# motherboard.net
KiCad netlist of a schematic drawn in EAGLE
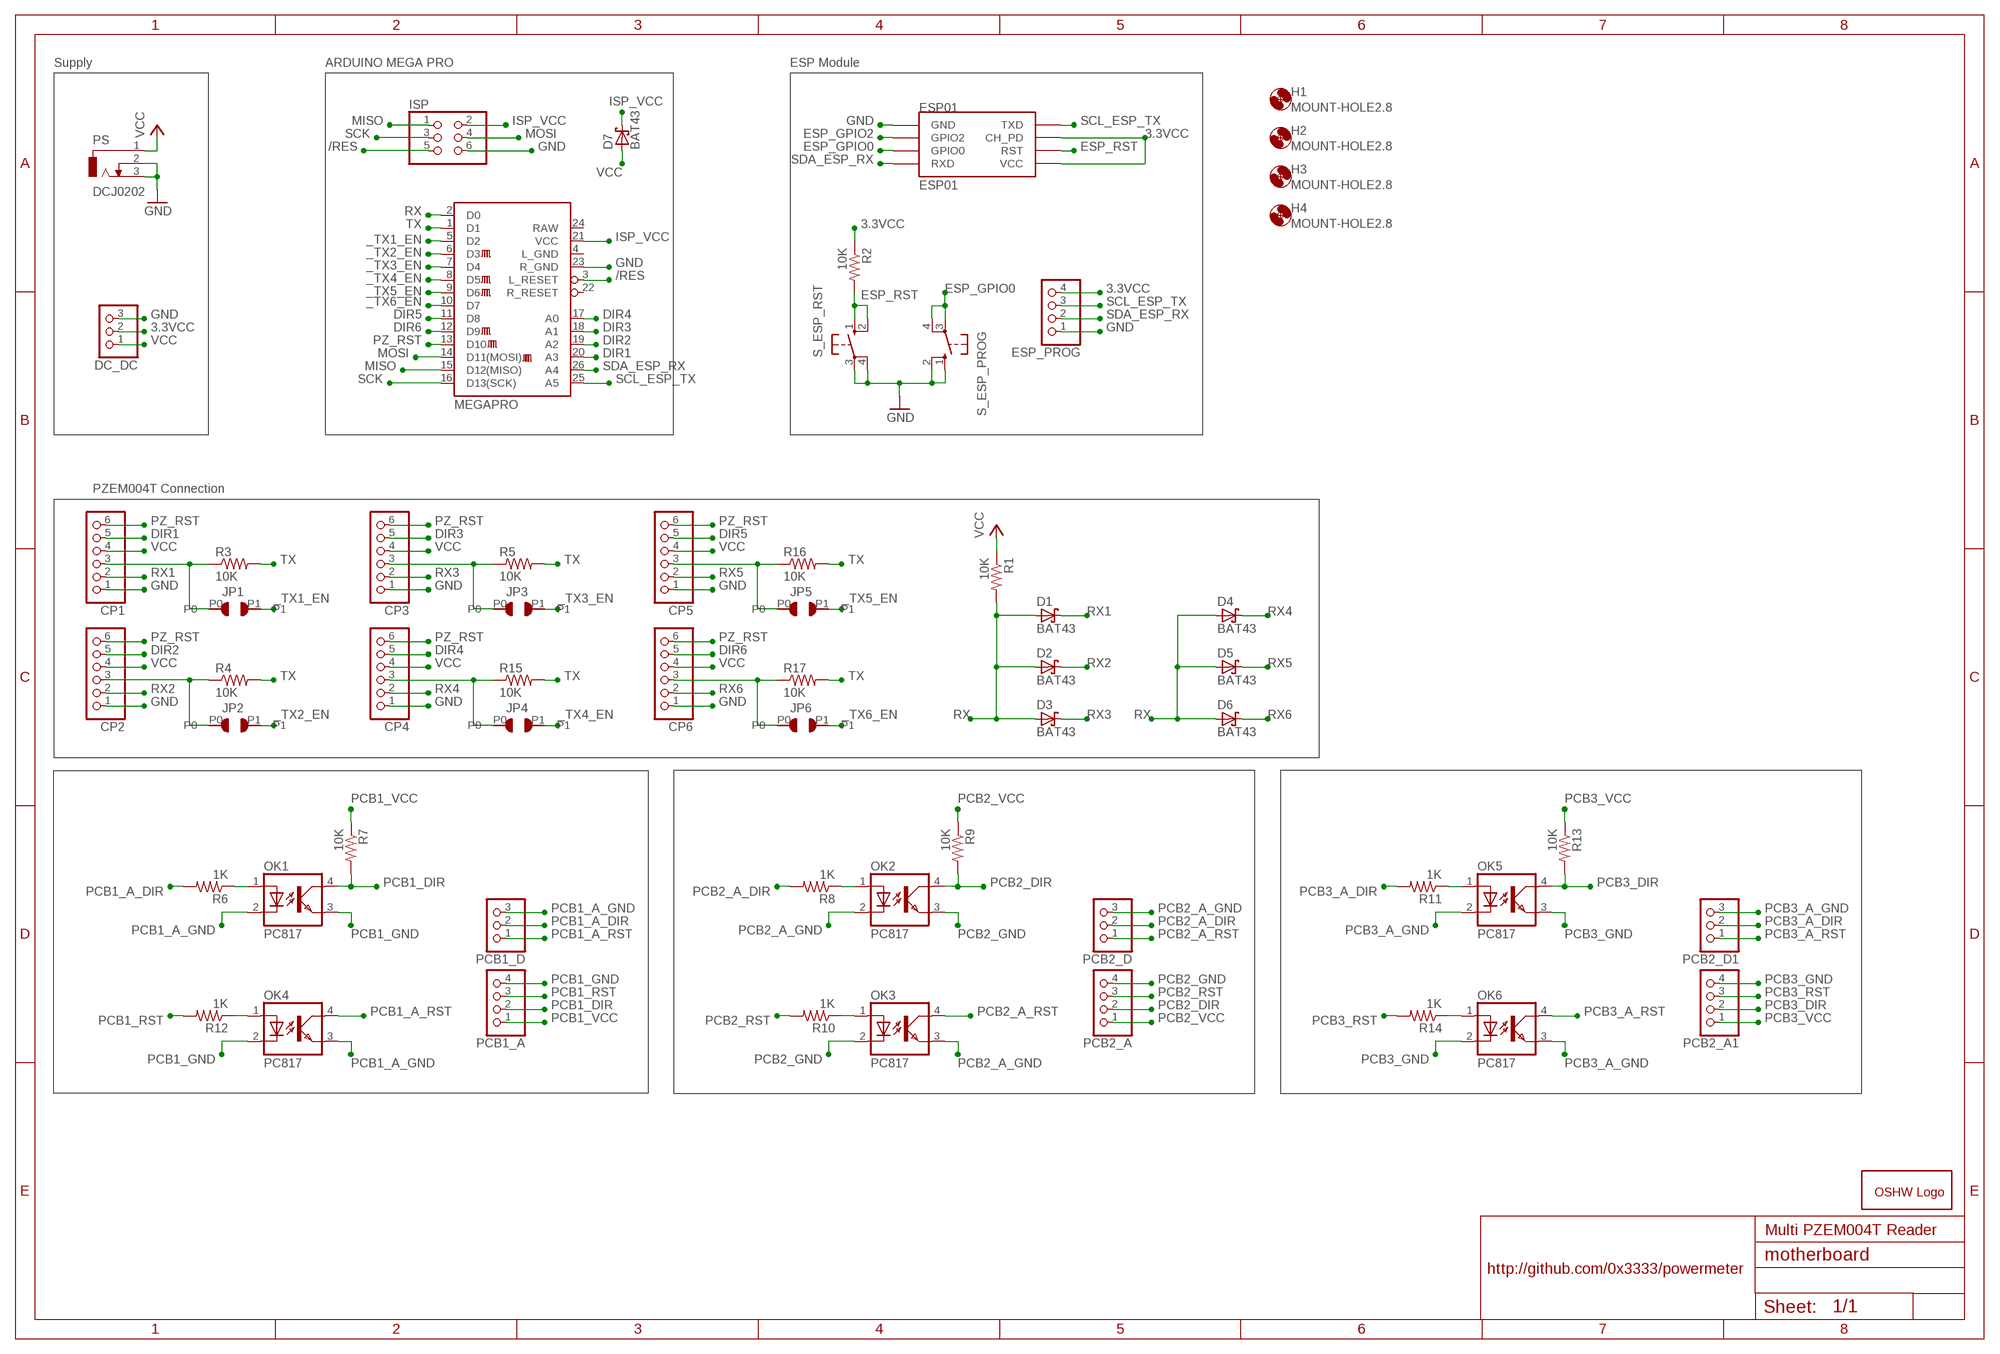
[diagram p0: schematic, sheet 1]

(export (version "E")
  (design (tool "Eeschema 10.0.6"))
  (components
    (comp (ref "CP1")
      (value "PINHD-1X6")
      (footprint "eagle-import:1X06")
      (libsource (lib "eagle-import") (part "PINHD-1X6"))
    )
    (comp (ref "CP2")
      (value "PINHD-1X6")
      (footprint "eagle-import:1X06")
      (libsource (lib "eagle-import") (part "PINHD-1X6"))
    )
    (comp (ref "CP3")
      (value "PINHD-1X6")
      (footprint "eagle-import:1X06")
      (libsource (lib "eagle-import") (part "PINHD-1X6"))
    )
    (comp (ref "CP4")
      (value "PINHD-1X6")
      (footprint "eagle-import:1X06")
      (libsource (lib "eagle-import") (part "PINHD-1X6"))
    )
    (comp (ref "CP5")
      (value "PINHD-1X6")
      (footprint "eagle-import:1X06")
      (libsource (lib "eagle-import") (part "PINHD-1X6"))
    )
    (comp (ref "CP6")
      (value "PINHD-1X6")
      (footprint "eagle-import:1X06")
      (libsource (lib "eagle-import") (part "PINHD-1X6"))
    )
    (comp (ref "D1")
      (value "BAT43")
      (footprint "eagle-import:SOD323_ST")
      (libsource (lib "eagle-import") (part "BAT60J"))
    )
    (comp (ref "D2")
      (value "BAT43")
      (footprint "eagle-import:SOD323_ST")
      (libsource (lib "eagle-import") (part "BAT60J"))
    )
    (comp (ref "D3")
      (value "BAT43")
      (footprint "eagle-import:SOD323_ST")
      (libsource (lib "eagle-import") (part "BAT60J"))
    )
    (comp (ref "D4")
      (value "BAT43")
      (footprint "eagle-import:SOD323_ST")
      (libsource (lib "eagle-import") (part "BAT60J"))
    )
    (comp (ref "D5")
      (value "BAT43")
      (footprint "eagle-import:SOD323_ST")
      (libsource (lib "eagle-import") (part "BAT60J"))
    )
    (comp (ref "D6")
      (value "BAT43")
      (footprint "eagle-import:SOD323_ST")
      (libsource (lib "eagle-import") (part "BAT60J"))
    )
    (comp (ref "D7")
      (value "BAT43")
      (footprint "eagle-import:SOD323_ST")
      (libsource (lib "eagle-import") (part "BAT60J"))
    )
    (comp (ref "DC_DC")
      (value "PINHD-1X3")
      (footprint "eagle-import:1X03")
      (libsource (lib "eagle-import") (part "PINHD-1X3"))
    )
    (comp (ref "ESP01")
      (value "ESP01")
      (footprint "eagle-import:ESP01")
      (libsource (lib "eagle-import") (part "ESP01"))
    )
    (comp (ref "ESP_PROG")
      (value "PINHD-1X4")
      (footprint "eagle-import:1X04")
      (libsource (lib "eagle-import") (part "PINHD-1X4"))
    )
    (comp (ref "GOLD_ORB_SM1")
      (value "OSHWLOGOLOGO8MM")
      (footprint "eagle-import:OSHW_8MM")
      (libsource (lib "eagle-import") (part "OSHWLOGOLOGO8MM"))
    )
    (comp (ref "H1")
      (value "MOUNT-HOLE2.8")
      (footprint "eagle-import:2,8")
      (libsource (lib "eagle-import") (part "MOUNT-HOLE2.8"))
    )
    (comp (ref "H2")
      (value "MOUNT-HOLE2.8")
      (footprint "eagle-import:2,8")
      (libsource (lib "eagle-import") (part "MOUNT-HOLE2.8"))
    )
    (comp (ref "H3")
      (value "MOUNT-HOLE2.8")
      (footprint "eagle-import:2,8")
      (libsource (lib "eagle-import") (part "MOUNT-HOLE2.8"))
    )
    (comp (ref "H4")
      (value "MOUNT-HOLE2.8")
      (footprint "eagle-import:2,8")
      (libsource (lib "eagle-import") (part "MOUNT-HOLE2.8"))
    )
    (comp (ref "ISP")
      (value "PINHD-2X3")
      (footprint "eagle-import:2X03")
      (libsource (lib "eagle-import") (part "PINHD-2X3"))
    )
    (comp (ref "JP1")
      (value "SMD_JUMPER")
      (footprint "eagle-import:SMD_JUMPER")
      (libsource (lib "eagle-import") (part "SMD_JUMPER"))
    )
    (comp (ref "JP2")
      (value "SMD_JUMPER")
      (footprint "eagle-import:SMD_JUMPER")
      (libsource (lib "eagle-import") (part "SMD_JUMPER"))
    )
    (comp (ref "JP3")
      (value "SMD_JUMPER")
      (footprint "eagle-import:SMD_JUMPER")
      (libsource (lib "eagle-import") (part "SMD_JUMPER"))
    )
    (comp (ref "JP4")
      (value "SMD_JUMPER")
      (footprint "eagle-import:SMD_JUMPER")
      (libsource (lib "eagle-import") (part "SMD_JUMPER"))
    )
    (comp (ref "JP5")
      (value "SMD_JUMPER")
      (footprint "eagle-import:SMD_JUMPER")
      (libsource (lib "eagle-import") (part "SMD_JUMPER"))
    )
    (comp (ref "JP6")
      (value "SMD_JUMPER")
      (footprint "eagle-import:SMD_JUMPER")
      (libsource (lib "eagle-import") (part "SMD_JUMPER"))
    )
    (comp (ref "MEGAPRO")
      (value "ARDUINO_PRO_MINI")
      (footprint "eagle-import:ARDUINO_PRO_MINI")
      (libsource (lib "eagle-import") (part "ARDUINO_PRO_MINI"))
    )
    (comp (ref "OK1")
      (value "PC817")
      (footprint "eagle-import:DIL04")
      (fields (field (name "MPN") "PC817X4J000F"))
      (libsource (lib "eagle-import") (part "PC817"))
    )
    (comp (ref "OK2")
      (value "PC817")
      (footprint "eagle-import:DIL04")
      (fields (field (name "MPN") "PC817X4J000F"))
      (libsource (lib "eagle-import") (part "PC817"))
    )
    (comp (ref "OK3")
      (value "PC817")
      (footprint "eagle-import:DIL04")
      (fields (field (name "MPN") "PC817X4J000F"))
      (libsource (lib "eagle-import") (part "PC817"))
    )
    (comp (ref "OK4")
      (value "PC817")
      (footprint "eagle-import:DIL04")
      (fields (field (name "MPN") "PC817X4J000F"))
      (libsource (lib "eagle-import") (part "PC817"))
    )
    (comp (ref "OK5")
      (value "PC817")
      (footprint "eagle-import:DIL04")
      (fields (field (name "MPN") "PC817X4J000F"))
      (libsource (lib "eagle-import") (part "PC817"))
    )
    (comp (ref "OK6")
      (value "PC817")
      (footprint "eagle-import:DIL04")
      (fields (field (name "MPN") "PC817X4J000F"))
      (libsource (lib "eagle-import") (part "PC817"))
    )
    (comp (ref "PCB1_A")
      (value "PINHD-1X4")
      (footprint "eagle-import:1X04")
      (libsource (lib "eagle-import") (part "PINHD-1X4"))
    )
    (comp (ref "PCB1_D")
      (value "PINHD-1X3")
      (footprint "eagle-import:1X03")
      (libsource (lib "eagle-import") (part "PINHD-1X3"))
    )
    (comp (ref "PCB2_A")
      (value "PINHD-1X4")
      (footprint "eagle-import:1X04")
      (libsource (lib "eagle-import") (part "PINHD-1X4"))
    )
    (comp (ref "PCB2_A1")
      (value "PINHD-1X4")
      (footprint "eagle-import:1X04")
      (libsource (lib "eagle-import") (part "PINHD-1X4"))
    )
    (comp (ref "PCB2_D")
      (value "PINHD-1X3")
      (footprint "eagle-import:1X03")
      (libsource (lib "eagle-import") (part "PINHD-1X3"))
    )
    (comp (ref "PCB2_D1")
      (value "PINHD-1X3")
      (footprint "eagle-import:1X03")
      (libsource (lib "eagle-import") (part "PINHD-1X3"))
    )
    (comp (ref "PS")
      (value "DCJ0202")
      (footprint "eagle-import:DCJ0202")
      (libsource (lib "eagle-import") (part "DCJ0202"))
    )
    (comp (ref "R1")
      (value "10K")
      (footprint "eagle-import:R1206W")
      (libsource (lib "eagle-import") (part "R-US_R1206W"))
    )
    (comp (ref "R2")
      (value "10K")
      (footprint "eagle-import:R0805")
      (libsource (lib "eagle-import") (part "R-US_R0805"))
    )
    (comp (ref "R3")
      (value "10K")
      (footprint "eagle-import:R1206W")
      (libsource (lib "eagle-import") (part "R-US_R1206W"))
    )
    (comp (ref "R4")
      (value "10K")
      (footprint "eagle-import:R1206W")
      (libsource (lib "eagle-import") (part "R-US_R1206W"))
    )
    (comp (ref "R5")
      (value "10K")
      (footprint "eagle-import:R1206W")
      (libsource (lib "eagle-import") (part "R-US_R1206W"))
    )
    (comp (ref "R6")
      (value "1K")
      (footprint "eagle-import:R0805")
      (libsource (lib "eagle-import") (part "R-US_R0805"))
    )
    (comp (ref "R7")
      (value "10K")
      (footprint "eagle-import:R0805")
      (libsource (lib "eagle-import") (part "R-US_R0805"))
    )
    (comp (ref "R8")
      (value "1K")
      (footprint "eagle-import:R0805")
      (libsource (lib "eagle-import") (part "R-US_R0805"))
    )
    (comp (ref "R9")
      (value "10K")
      (footprint "eagle-import:R0805")
      (libsource (lib "eagle-import") (part "R-US_R0805"))
    )
    (comp (ref "R10")
      (value "1K")
      (footprint "eagle-import:R0805")
      (libsource (lib "eagle-import") (part "R-US_R0805"))
    )
    (comp (ref "R11")
      (value "1K")
      (footprint "eagle-import:R0805")
      (libsource (lib "eagle-import") (part "R-US_R0805"))
    )
    (comp (ref "R12")
      (value "1K")
      (footprint "eagle-import:R0805")
      (libsource (lib "eagle-import") (part "R-US_R0805"))
    )
    (comp (ref "R13")
      (value "10K")
      (footprint "eagle-import:R0805")
      (libsource (lib "eagle-import") (part "R-US_R0805"))
    )
    (comp (ref "R14")
      (value "1K")
      (footprint "eagle-import:R0805")
      (libsource (lib "eagle-import") (part "R-US_R0805"))
    )
    (comp (ref "R15")
      (value "10K")
      (footprint "eagle-import:R1206W")
      (libsource (lib "eagle-import") (part "R-US_R1206W"))
    )
    (comp (ref "R16")
      (value "10K")
      (footprint "eagle-import:R1206W")
      (libsource (lib "eagle-import") (part "R-US_R1206W"))
    )
    (comp (ref "R17")
      (value "10K")
      (footprint "eagle-import:R1206W")
      (libsource (lib "eagle-import") (part "R-US_R1206W"))
    )
    (comp (ref "S_ESP_PROG")
      (value "10-XX")
      (footprint "eagle-import:B3F-10XX")
      (fields (field (name "MPN") "B3F-1000"))
      (libsource (lib "eagle-import") (part "10-XX"))
    )
    (comp (ref "S_ESP_RST")
      (value "10-XX")
      (footprint "eagle-import:B3F-10XX")
      (fields (field (name "MPN") "B3F-1000"))
      (libsource (lib "eagle-import") (part "10-XX"))
    )
  )
  (nets
    (net (code "1") (name "/3.3VCC") (class "Default")
      (node (ref "DC_DC") (pin "2") (pinfunction "2_2") (pintype "passive"))
      (node (ref "ESP01") (pin "CH_PD") (pinfunction "CH_PD_CH_PD") (pintype "bidirectional"))
      (node (ref "ESP01") (pin "VCC") (pinfunction "VCC_VCC") (pintype "bidirectional"))
      (node (ref "ESP_PROG") (pin "4") (pinfunction "4_4") (pintype "passive"))
      (node (ref "R2") (pin "1") (pinfunction "1_1") (pintype "passive"))
    )
    (net (code "2") (name "/DIR1") (class "Default")
      (node (ref "CP1") (pin "5") (pinfunction "5_5") (pintype "passive"))
      (node (ref "MEGAPRO") (pin "20") (pinfunction "A3_20") (pintype "bidirectional"))
    )
    (net (code "3") (name "/DIR2") (class "Default")
      (node (ref "CP2") (pin "5") (pinfunction "5_5") (pintype "passive"))
      (node (ref "MEGAPRO") (pin "19") (pinfunction "A2_19") (pintype "bidirectional"))
    )
    (net (code "4") (name "/DIR3") (class "Default")
      (node (ref "CP3") (pin "5") (pinfunction "5_5") (pintype "passive"))
      (node (ref "MEGAPRO") (pin "18") (pinfunction "A1_18") (pintype "bidirectional"))
    )
    (net (code "5") (name "/DIR4") (class "Default")
      (node (ref "CP4") (pin "5") (pinfunction "5_5") (pintype "passive"))
      (node (ref "MEGAPRO") (pin "17") (pinfunction "A0_17") (pintype "bidirectional"))
    )
    (net (code "6") (name "/DIR5") (class "Default")
      (node (ref "CP5") (pin "5") (pinfunction "5_5") (pintype "passive"))
      (node (ref "MEGAPRO") (pin "11") (pinfunction "D8_11") (pintype "bidirectional"))
    )
    (net (code "7") (name "/DIR6") (class "Default")
      (node (ref "CP6") (pin "5") (pinfunction "5_5") (pintype "passive"))
      (node (ref "MEGAPRO") (pin "12") (pinfunction "D9_12") (pintype "bidirectional"))
    )
    (net (code "8") (name "/ESP_GPIO0") (class "Default")
      (node (ref "ESP01") (pin "GPIO0") (pinfunction "GPIO0_GPIO0") (pintype "bidirectional"))
      (node (ref "S_ESP_PROG") (pin "3") (pinfunction "P_3") (pintype "passive"))
      (node (ref "S_ESP_PROG") (pin "4") (pinfunction "P1_4") (pintype "passive"))
    )
    (net (code "9") (name "/ESP_GPIO2") (class "Default")
      (node (ref "ESP01") (pin "GPIO2") (pinfunction "GPIO2_GPIO2") (pintype "bidirectional"))
    )
    (net (code "10") (name "/ESP_RST") (class "Default")
      (node (ref "ESP01") (pin "RST") (pinfunction "RST_RST") (pintype "bidirectional"))
      (node (ref "R2") (pin "2") (pinfunction "2_2") (pintype "passive"))
      (node (ref "S_ESP_RST") (pin "1") (pinfunction "S_1") (pintype "passive"))
      (node (ref "S_ESP_RST") (pin "2") (pinfunction "S1_2") (pintype "passive"))
    )
    (net (code "11") (name "/ISP_VCC") (class "Default")
      (node (ref "D7") (pin "C") (pinfunction "C_C") (pintype "passive"))
      (node (ref "ISP") (pin "2") (pinfunction "2_2") (pintype "passive"))
      (node (ref "MEGAPRO") (pin "21") (pinfunction "VCC_21") (pintype "bidirectional"))
    )
    (net (code "12") (name "/MISO") (class "Default")
      (node (ref "ISP") (pin "1") (pinfunction "1_1") (pintype "passive"))
      (node (ref "MEGAPRO") (pin "15") (pinfunction "D12(MISO)_15") (pintype "bidirectional"))
    )
    (net (code "13") (name "/MOSI") (class "Default")
      (node (ref "ISP") (pin "4") (pinfunction "4_4") (pintype "passive"))
      (node (ref "MEGAPRO") (pin "14") (pinfunction "D11(MOSI)_14") (pintype "bidirectional"))
    )
    (net (code "14") (name "/PCB1_A_DIR") (class "Default")
      (node (ref "PCB1_D") (pin "2") (pinfunction "2_2") (pintype "passive"))
      (node (ref "R6") (pin "2") (pinfunction "2_2") (pintype "passive"))
    )
    (net (code "15") (name "/PCB1_A_GND") (class "Default")
      (node (ref "OK1") (pin "2") (pinfunction "C_2") (pintype "passive"))
      (node (ref "OK4") (pin "3") (pinfunction "EMIT_3") (pintype "passive"))
      (node (ref "PCB1_D") (pin "3") (pinfunction "3_3") (pintype "passive"))
    )
    (net (code "16") (name "/PCB1_A_RST") (class "Default")
      (node (ref "OK4") (pin "4") (pinfunction "COL_4") (pintype "passive"))
      (node (ref "PCB1_D") (pin "1") (pinfunction "1_1") (pintype "passive"))
    )
    (net (code "17") (name "/PCB1_DIR") (class "Default")
      (node (ref "OK1") (pin "4") (pinfunction "COL_4") (pintype "passive"))
      (node (ref "PCB1_A") (pin "2") (pinfunction "2_2") (pintype "passive"))
      (node (ref "R7") (pin "2") (pinfunction "2_2") (pintype "passive"))
    )
    (net (code "18") (name "/PCB1_GND") (class "Default")
      (node (ref "OK1") (pin "3") (pinfunction "EMIT_3") (pintype "passive"))
      (node (ref "OK4") (pin "2") (pinfunction "C_2") (pintype "passive"))
      (node (ref "PCB1_A") (pin "4") (pinfunction "4_4") (pintype "passive"))
    )
    (net (code "19") (name "/PCB1_RST") (class "Default")
      (node (ref "PCB1_A") (pin "3") (pinfunction "3_3") (pintype "passive"))
      (node (ref "R12") (pin "2") (pinfunction "2_2") (pintype "passive"))
    )
    (net (code "20") (name "/PCB1_VCC") (class "Default")
      (node (ref "PCB1_A") (pin "1") (pinfunction "1_1") (pintype "passive"))
      (node (ref "R7") (pin "1") (pinfunction "1_1") (pintype "passive"))
    )
    (net (code "21") (name "/PCB2_A_DIR") (class "Default")
      (node (ref "PCB2_D") (pin "2") (pinfunction "2_2") (pintype "passive"))
      (node (ref "R8") (pin "2") (pinfunction "2_2") (pintype "passive"))
    )
    (net (code "22") (name "/PCB2_A_GND") (class "Default")
      (node (ref "OK2") (pin "2") (pinfunction "C_2") (pintype "passive"))
      (node (ref "OK3") (pin "3") (pinfunction "EMIT_3") (pintype "passive"))
      (node (ref "PCB2_D") (pin "3") (pinfunction "3_3") (pintype "passive"))
    )
    (net (code "23") (name "/PCB2_A_RST") (class "Default")
      (node (ref "OK3") (pin "4") (pinfunction "COL_4") (pintype "passive"))
      (node (ref "PCB2_D") (pin "1") (pinfunction "1_1") (pintype "passive"))
    )
    (net (code "24") (name "/PCB2_DIR") (class "Default")
      (node (ref "OK2") (pin "4") (pinfunction "COL_4") (pintype "passive"))
      (node (ref "PCB2_A") (pin "2") (pinfunction "2_2") (pintype "passive"))
      (node (ref "R9") (pin "2") (pinfunction "2_2") (pintype "passive"))
    )
    (net (code "25") (name "/PCB2_GND") (class "Default")
      (node (ref "OK2") (pin "3") (pinfunction "EMIT_3") (pintype "passive"))
      (node (ref "OK3") (pin "2") (pinfunction "C_2") (pintype "passive"))
      (node (ref "PCB2_A") (pin "4") (pinfunction "4_4") (pintype "passive"))
    )
    (net (code "26") (name "/PCB2_RST") (class "Default")
      (node (ref "PCB2_A") (pin "3") (pinfunction "3_3") (pintype "passive"))
      (node (ref "R10") (pin "2") (pinfunction "2_2") (pintype "passive"))
    )
    (net (code "27") (name "/PCB2_VCC") (class "Default")
      (node (ref "PCB2_A") (pin "1") (pinfunction "1_1") (pintype "passive"))
      (node (ref "R9") (pin "1") (pinfunction "1_1") (pintype "passive"))
    )
    (net (code "28") (name "/PCB3_A_DIR") (class "Default")
      (node (ref "PCB2_D1") (pin "2") (pinfunction "2_2") (pintype "passive"))
      (node (ref "R11") (pin "2") (pinfunction "2_2") (pintype "passive"))
    )
    (net (code "29") (name "/PCB3_A_GND") (class "Default")
      (node (ref "OK5") (pin "2") (pinfunction "C_2") (pintype "passive"))
      (node (ref "OK6") (pin "3") (pinfunction "EMIT_3") (pintype "passive"))
      (node (ref "PCB2_D1") (pin "3") (pinfunction "3_3") (pintype "passive"))
    )
    (net (code "30") (name "/PCB3_A_RST") (class "Default")
      (node (ref "OK6") (pin "4") (pinfunction "COL_4") (pintype "passive"))
      (node (ref "PCB2_D1") (pin "1") (pinfunction "1_1") (pintype "passive"))
    )
    (net (code "31") (name "/PCB3_DIR") (class "Default")
      (node (ref "OK5") (pin "4") (pinfunction "COL_4") (pintype "passive"))
      (node (ref "PCB2_A1") (pin "2") (pinfunction "2_2") (pintype "passive"))
      (node (ref "R13") (pin "2") (pinfunction "2_2") (pintype "passive"))
    )
    (net (code "32") (name "/PCB3_GND") (class "Default")
      (node (ref "OK5") (pin "3") (pinfunction "EMIT_3") (pintype "passive"))
      (node (ref "OK6") (pin "2") (pinfunction "C_2") (pintype "passive"))
      (node (ref "PCB2_A1") (pin "4") (pinfunction "4_4") (pintype "passive"))
    )
    (net (code "33") (name "/PCB3_RST") (class "Default")
      (node (ref "PCB2_A1") (pin "3") (pinfunction "3_3") (pintype "passive"))
      (node (ref "R14") (pin "2") (pinfunction "2_2") (pintype "passive"))
    )
    (net (code "34") (name "/PCB3_VCC") (class "Default")
      (node (ref "PCB2_A1") (pin "1") (pinfunction "1_1") (pintype "passive"))
      (node (ref "R13") (pin "1") (pinfunction "1_1") (pintype "passive"))
    )
    (net (code "35") (name "/PZ_RST") (class "Default")
      (node (ref "CP1") (pin "6") (pinfunction "6_6") (pintype "passive"))
      (node (ref "CP2") (pin "6") (pinfunction "6_6") (pintype "passive"))
      (node (ref "CP3") (pin "6") (pinfunction "6_6") (pintype "passive"))
      (node (ref "CP4") (pin "6") (pinfunction "6_6") (pintype "passive"))
      (node (ref "CP5") (pin "6") (pinfunction "6_6") (pintype "passive"))
      (node (ref "CP6") (pin "6") (pinfunction "6_6") (pintype "passive"))
      (node (ref "MEGAPRO") (pin "13") (pinfunction "D10_13") (pintype "bidirectional"))
    )
    (net (code "36") (name "/RX") (class "Default")
      (node (ref "D1") (pin "A") (pinfunction "A_A") (pintype "passive"))
      (node (ref "D2") (pin "A") (pinfunction "A_A") (pintype "passive"))
      (node (ref "D3") (pin "A") (pinfunction "A_A") (pintype "passive"))
      (node (ref "D4") (pin "A") (pinfunction "A_A") (pintype "passive"))
      (node (ref "D5") (pin "A") (pinfunction "A_A") (pintype "passive"))
      (node (ref "D6") (pin "A") (pinfunction "A_A") (pintype "passive"))
      (node (ref "MEGAPRO") (pin "2") (pinfunction "D0_2") (pintype "bidirectional"))
      (node (ref "R1") (pin "2") (pinfunction "2_2") (pintype "passive"))
    )
    (net (code "37") (name "/RX1") (class "Default")
      (node (ref "CP1") (pin "2") (pinfunction "2_2") (pintype "passive"))
      (node (ref "D1") (pin "C") (pinfunction "C_C") (pintype "passive"))
    )
    (net (code "38") (name "/RX2") (class "Default")
      (node (ref "CP2") (pin "2") (pinfunction "2_2") (pintype "passive"))
      (node (ref "D2") (pin "C") (pinfunction "C_C") (pintype "passive"))
    )
    (net (code "39") (name "/RX3") (class "Default")
      (node (ref "CP3") (pin "2") (pinfunction "2_2") (pintype "passive"))
      (node (ref "D3") (pin "C") (pinfunction "C_C") (pintype "passive"))
    )
    (net (code "40") (name "/RX4") (class "Default")
      (node (ref "CP4") (pin "2") (pinfunction "2_2") (pintype "passive"))
      (node (ref "D4") (pin "C") (pinfunction "C_C") (pintype "passive"))
    )
    (net (code "41") (name "/RX5") (class "Default")
      (node (ref "CP5") (pin "2") (pinfunction "2_2") (pintype "passive"))
      (node (ref "D5") (pin "C") (pinfunction "C_C") (pintype "passive"))
    )
    (net (code "42") (name "/RX6") (class "Default")
      (node (ref "CP6") (pin "2") (pinfunction "2_2") (pintype "passive"))
      (node (ref "D6") (pin "C") (pinfunction "C_C") (pintype "passive"))
    )
    (net (code "43") (name "/SCK") (class "Default")
      (node (ref "ISP") (pin "3") (pinfunction "3_3") (pintype "passive"))
      (node (ref "MEGAPRO") (pin "16") (pinfunction "D13(SCK)_16") (pintype "bidirectional"))
    )
    (net (code "44") (name "/SCL_ESP_TX") (class "Default")
      (node (ref "ESP01") (pin "TX") (pinfunction "TXD_TX") (pintype "bidirectional"))
      (node (ref "ESP_PROG") (pin "3") (pinfunction "3_3") (pintype "passive"))
      (node (ref "MEGAPRO") (pin "25") (pinfunction "A5_25") (pintype "bidirectional"))
    )
    (net (code "45") (name "/SDA_ESP_RX") (class "Default")
      (node (ref "ESP01") (pin "RX") (pinfunction "RXD_RX") (pintype "bidirectional"))
      (node (ref "ESP_PROG") (pin "2") (pinfunction "2_2") (pintype "passive"))
      (node (ref "MEGAPRO") (pin "26") (pinfunction "A4_26") (pintype "bidirectional"))
    )
    (net (code "46") (name "/TX") (class "Default")
      (node (ref "MEGAPRO") (pin "1") (pinfunction "D1_1") (pintype "bidirectional"))
      (node (ref "R15") (pin "2") (pinfunction "2_2") (pintype "passive"))
      (node (ref "R16") (pin "2") (pinfunction "2_2") (pintype "passive"))
      (node (ref "R17") (pin "2") (pinfunction "2_2") (pintype "passive"))
      (node (ref "R3") (pin "2") (pinfunction "2_2") (pintype "passive"))
      (node (ref "R4") (pin "2") (pinfunction "2_2") (pintype "passive"))
      (node (ref "R5") (pin "2") (pinfunction "2_2") (pintype "passive"))
    )
    (net (code "47") (name "/_TX1_EN") (class "Default")
      (node (ref "JP1") (pin "P1") (pinfunction "P1_P1") (pintype "bidirectional"))
      (node (ref "MEGAPRO") (pin "5") (pinfunction "D2_5") (pintype "bidirectional"))
    )
    (net (code "48") (name "/_TX2_EN") (class "Default")
      (node (ref "JP2") (pin "P1") (pinfunction "P1_P1") (pintype "bidirectional"))
      (node (ref "MEGAPRO") (pin "6") (pinfunction "D3_6") (pintype "bidirectional"))
    )
    (net (code "49") (name "/_TX3_EN") (class "Default")
      (node (ref "JP3") (pin "P1") (pinfunction "P1_P1") (pintype "bidirectional"))
      (node (ref "MEGAPRO") (pin "7") (pinfunction "D4_7") (pintype "bidirectional"))
    )
    (net (code "50") (name "/_TX4_EN") (class "Default")
      (node (ref "JP4") (pin "P1") (pinfunction "P1_P1") (pintype "bidirectional"))
      (node (ref "MEGAPRO") (pin "8") (pinfunction "D5_8") (pintype "bidirectional"))
    )
    (net (code "51") (name "/_TX5_EN") (class "Default")
      (node (ref "JP5") (pin "P1") (pinfunction "P1_P1") (pintype "bidirectional"))
      (node (ref "MEGAPRO") (pin "9") (pinfunction "D6_9") (pintype "bidirectional"))
    )
    (net (code "52") (name "/_TX6_EN") (class "Default")
      (node (ref "JP6") (pin "P1") (pinfunction "P1_P1") (pintype "bidirectional"))
      (node (ref "MEGAPRO") (pin "10") (pinfunction "D7_10") (pintype "bidirectional"))
    )
    (net (code "53") (name "/{slash}RES") (class "Default")
      (node (ref "ISP") (pin "5") (pinfunction "5_5") (pintype "passive"))
      (node (ref "MEGAPRO") (pin "3") (pinfunction "L_RESET_3") (pintype "bidirectional"))
    )
    (net (code "54") (name "GND") (class "Default")
      (node (ref "CP1") (pin "1") (pinfunction "1_1") (pintype "passive"))
      (node (ref "CP2") (pin "1") (pinfunction "1_1") (pintype "passive"))
      (node (ref "CP3") (pin "1") (pinfunction "1_1") (pintype "passive"))
      (node (ref "CP4") (pin "1") (pinfunction "1_1") (pintype "passive"))
      (node (ref "CP5") (pin "1") (pinfunction "1_1") (pintype "passive"))
      (node (ref "CP6") (pin "1") (pinfunction "1_1") (pintype "passive"))
      (node (ref "DC_DC") (pin "3") (pinfunction "3_3") (pintype "passive"))
      (node (ref "ESP01") (pin "GND") (pinfunction "GND_GND") (pintype "bidirectional"))
      (node (ref "ESP_PROG") (pin "1") (pinfunction "1_1") (pintype "passive"))
      (node (ref "ISP") (pin "6") (pinfunction "6_6") (pintype "passive"))
      (node (ref "MEGAPRO") (pin "23") (pinfunction "R_GND_23") (pintype "bidirectional"))
      (node (ref "PS") (pin "2") (pinfunction "2_2") (pintype "passive"))
      (node (ref "PS") (pin "3") (pinfunction "3_3") (pintype "passive"))
      (node (ref "S_ESP_PROG") (pin "1") (pinfunction "S_1") (pintype "passive"))
      (node (ref "S_ESP_PROG") (pin "2") (pinfunction "S1_2") (pintype "passive"))
      (node (ref "S_ESP_RST") (pin "3") (pinfunction "P_3") (pintype "passive"))
      (node (ref "S_ESP_RST") (pin "4") (pinfunction "P1_4") (pintype "passive"))
    )
    (net (code "55") (name "Net-(CP1-Pad3)") (class "Default")
      (node (ref "CP1") (pin "3") (pinfunction "3_3") (pintype "passive"))
      (node (ref "JP1") (pin "P0") (pinfunction "P0_P0") (pintype "bidirectional"))
      (node (ref "R3") (pin "1") (pinfunction "1_1") (pintype "passive"))
    )
    (net (code "56") (name "Net-(CP2-Pad3)") (class "Default")
      (node (ref "CP2") (pin "3") (pinfunction "3_3") (pintype "passive"))
      (node (ref "JP2") (pin "P0") (pinfunction "P0_P0") (pintype "bidirectional"))
      (node (ref "R4") (pin "1") (pinfunction "1_1") (pintype "passive"))
    )
    (net (code "57") (name "Net-(CP3-Pad3)") (class "Default")
      (node (ref "CP3") (pin "3") (pinfunction "3_3") (pintype "passive"))
      (node (ref "JP3") (pin "P0") (pinfunction "P0_P0") (pintype "bidirectional"))
      (node (ref "R5") (pin "1") (pinfunction "1_1") (pintype "passive"))
    )
    (net (code "58") (name "Net-(CP4-Pad3)") (class "Default")
      (node (ref "CP4") (pin "3") (pinfunction "3_3") (pintype "passive"))
      (node (ref "JP4") (pin "P0") (pinfunction "P0_P0") (pintype "bidirectional"))
      (node (ref "R15") (pin "1") (pinfunction "1_1") (pintype "passive"))
    )
    (net (code "59") (name "Net-(CP5-Pad3)") (class "Default")
      (node (ref "CP5") (pin "3") (pinfunction "3_3") (pintype "passive"))
      (node (ref "JP5") (pin "P0") (pinfunction "P0_P0") (pintype "bidirectional"))
      (node (ref "R16") (pin "1") (pinfunction "1_1") (pintype "passive"))
    )
    (net (code "60") (name "Net-(CP6-Pad3)") (class "Default")
      (node (ref "CP6") (pin "3") (pinfunction "3_3") (pintype "passive"))
      (node (ref "JP6") (pin "P0") (pinfunction "P0_P0") (pintype "bidirectional"))
      (node (ref "R17") (pin "1") (pinfunction "1_1") (pintype "passive"))
    )
    (net (code "61") (name "Net-(OK1-A)") (class "Default")
      (node (ref "OK1") (pin "1") (pinfunction "A_1") (pintype "passive"))
      (node (ref "R6") (pin "1") (pinfunction "1_1") (pintype "passive"))
    )
    (net (code "62") (name "Net-(OK2-A)") (class "Default")
      (node (ref "OK2") (pin "1") (pinfunction "A_1") (pintype "passive"))
      (node (ref "R8") (pin "1") (pinfunction "1_1") (pintype "passive"))
    )
    (net (code "63") (name "Net-(OK3-A)") (class "Default")
      (node (ref "OK3") (pin "1") (pinfunction "A_1") (pintype "passive"))
      (node (ref "R10") (pin "1") (pinfunction "1_1") (pintype "passive"))
    )
    (net (code "64") (name "Net-(OK4-A)") (class "Default")
      (node (ref "OK4") (pin "1") (pinfunction "A_1") (pintype "passive"))
      (node (ref "R12") (pin "1") (pinfunction "1_1") (pintype "passive"))
    )
    (net (code "65") (name "Net-(OK5-A)") (class "Default")
      (node (ref "OK5") (pin "1") (pinfunction "A_1") (pintype "passive"))
      (node (ref "R11") (pin "1") (pinfunction "1_1") (pintype "passive"))
    )
    (net (code "66") (name "Net-(OK6-A)") (class "Default")
      (node (ref "OK6") (pin "1") (pinfunction "A_1") (pintype "passive"))
      (node (ref "R14") (pin "1") (pinfunction "1_1") (pintype "passive"))
    )
    (net (code "67") (name "VCC") (class "Default")
      (node (ref "CP1") (pin "4") (pinfunction "4_4") (pintype "passive"))
      (node (ref "CP2") (pin "4") (pinfunction "4_4") (pintype "passive"))
      (node (ref "CP3") (pin "4") (pinfunction "4_4") (pintype "passive"))
      (node (ref "CP4") (pin "4") (pinfunction "4_4") (pintype "passive"))
      (node (ref "CP5") (pin "4") (pinfunction "4_4") (pintype "passive"))
      (node (ref "CP6") (pin "4") (pinfunction "4_4") (pintype "passive"))
      (node (ref "D7") (pin "A") (pinfunction "A_A") (pintype "passive"))
      (node (ref "DC_DC") (pin "1") (pinfunction "1_1") (pintype "passive"))
      (node (ref "PS") (pin "1") (pinfunction "1_1") (pintype "passive"))
      (node (ref "R1") (pin "1") (pinfunction "1_1") (pintype "passive"))
    )
    (net (code "68") (name "unconnected-(MEGAPRO-L_GND-Pad4)") (class "Default")
      (node (ref "MEGAPRO") (pin "4") (pinfunction "L_GND_4") (pintype "bidirectional"))
    )
    (net (code "69") (name "unconnected-(MEGAPRO-RAW-Pad24)") (class "Default")
      (node (ref "MEGAPRO") (pin "24") (pinfunction "RAW_24") (pintype "bidirectional"))
    )
    (net (code "70") (name "unconnected-(MEGAPRO-R_RESET-Pad22)") (class "Default")
      (node (ref "MEGAPRO") (pin "22") (pinfunction "R_RESET_22") (pintype "bidirectional"))
    )
  )
)
